# h-bridge2-smd-001.net
KiCad netlist of a schematic drawn in EAGLE
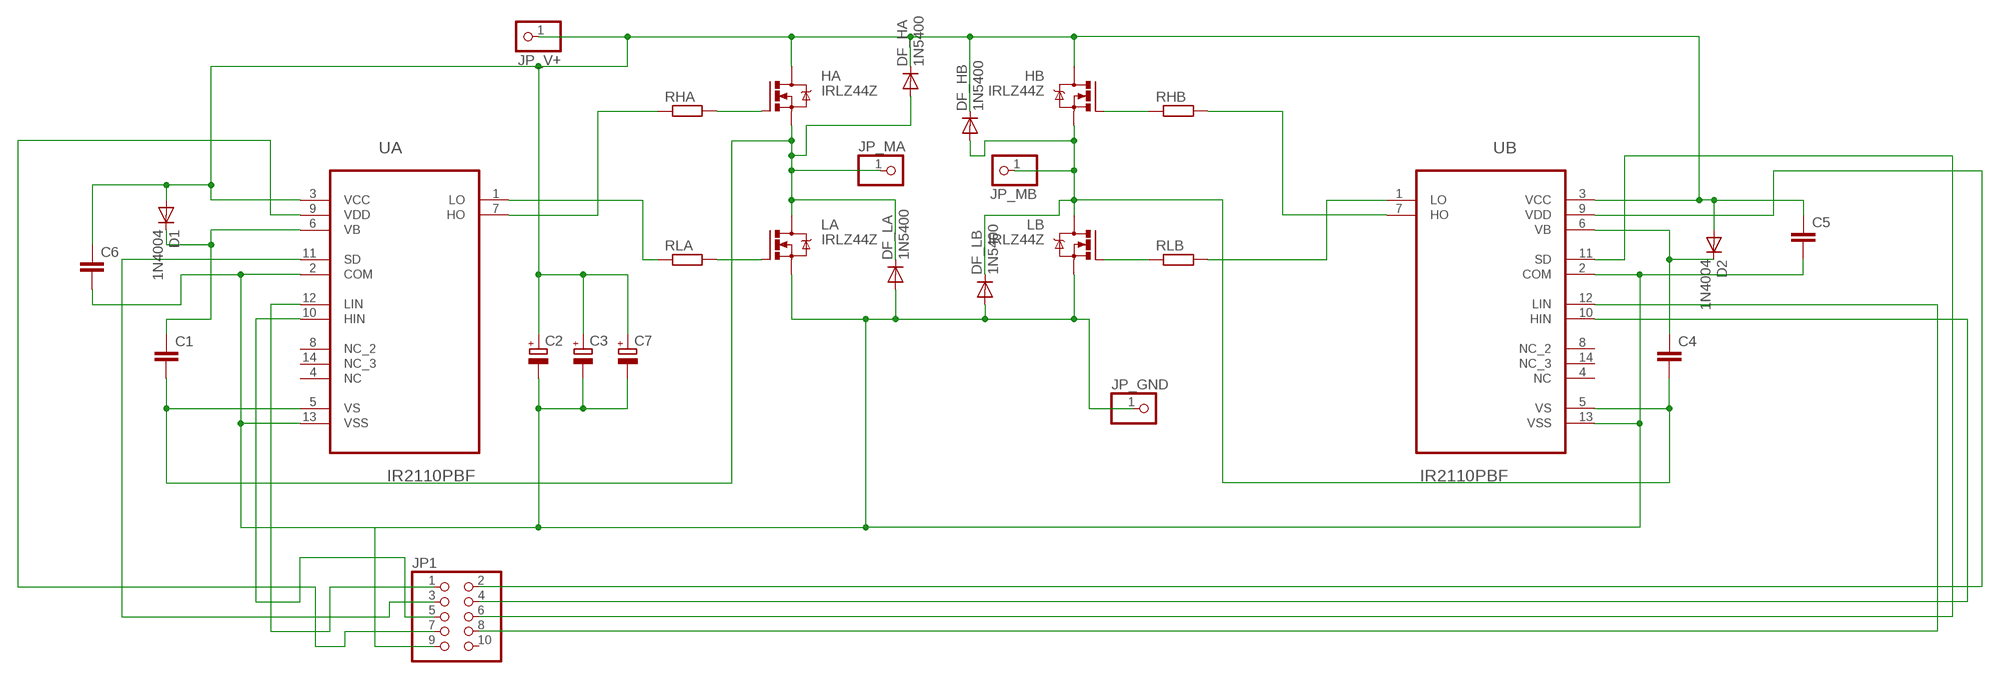
[diagram p0: schematic, sheet 1]

(export (version "E")
  (design (tool "Eeschema 10.0.6"))
  (components
    (comp (ref "C1")
      (value "C-EU025-025X050")
      (footprint "eagle-import:C025-025X050")
      (libsource (lib "eagle-import") (part "C-EU025-025X050"))
    )
    (comp (ref "C2")
      (value "CPOL-EUE5-13")
      (footprint "eagle-import:E5-13")
      (libsource (lib "eagle-import") (part "CPOL-EUE5-13"))
    )
    (comp (ref "C3")
      (value "CPOL-EUE5-13")
      (footprint "eagle-import:E5-13")
      (libsource (lib "eagle-import") (part "CPOL-EUE5-13"))
    )
    (comp (ref "C4")
      (value "C-EU025-025X050")
      (footprint "eagle-import:C025-025X050")
      (libsource (lib "eagle-import") (part "C-EU025-025X050"))
    )
    (comp (ref "C5")
      (value "C-EU025-025X050")
      (footprint "eagle-import:C025-025X050")
      (libsource (lib "eagle-import") (part "C-EU025-025X050"))
    )
    (comp (ref "C6")
      (value "C-EU025-025X050")
      (footprint "eagle-import:C025-025X050")
      (libsource (lib "eagle-import") (part "C-EU025-025X050"))
    )
    (comp (ref "C7")
      (value "CPOL-EUE5-13")
      (footprint "eagle-import:E5-13")
      (libsource (lib "eagle-import") (part "CPOL-EUE5-13"))
    )
    (comp (ref "D1")
      (value "1N4004")
      (footprint "eagle-import:DO41-10")
      (libsource (lib "eagle-import") (part "1N4004"))
    )
    (comp (ref "D2")
      (value "1N4004")
      (footprint "eagle-import:DO41-10")
      (libsource (lib "eagle-import") (part "1N4004"))
    )
    (comp (ref "DF_HA")
      (value "1N5400")
      (footprint "eagle-import:DO201-15")
      (libsource (lib "eagle-import") (part "1N5400"))
    )
    (comp (ref "DF_HB")
      (value "1N5400")
      (footprint "eagle-import:DO201-15")
      (libsource (lib "eagle-import") (part "1N5400"))
    )
    (comp (ref "DF_LA")
      (value "1N5400")
      (footprint "eagle-import:DO201-15")
      (libsource (lib "eagle-import") (part "1N5400"))
    )
    (comp (ref "DF_LB")
      (value "1N5400")
      (footprint "eagle-import:DO201-15")
      (libsource (lib "eagle-import") (part "1N5400"))
    )
    (comp (ref "HA")
      (value "IRLZ44Z")
      (footprint "eagle-import:TO220BH")
      (libsource (lib "eagle-import") (part "IRLZ44Z"))
    )
    (comp (ref "HB")
      (value "IRLZ44Z")
      (footprint "eagle-import:TO220BH")
      (libsource (lib "eagle-import") (part "IRLZ44Z"))
    )
    (comp (ref "JP1")
      (value "PINHD-2X5")
      (footprint "eagle-import:2X05")
      (libsource (lib "eagle-import") (part "PINHD-2X5"))
    )
    (comp (ref "JP_GND")
      (value "PINHD-1X1")
      (footprint "eagle-import:1X01")
      (libsource (lib "eagle-import") (part "PINHD-1X1"))
    )
    (comp (ref "JP_MA")
      (value "PINHD-1X1")
      (footprint "eagle-import:1X01")
      (libsource (lib "eagle-import") (part "PINHD-1X1"))
    )
    (comp (ref "JP_MB")
      (value "PINHD-1X1")
      (footprint "eagle-import:1X01")
      (libsource (lib "eagle-import") (part "PINHD-1X1"))
    )
    (comp (ref "JP_V+")
      (value "PINHD-1X1")
      (footprint "eagle-import:1X01")
      (libsource (lib "eagle-import") (part "PINHD-1X1"))
    )
    (comp (ref "LA")
      (value "IRLZ44Z")
      (footprint "eagle-import:TO220BH")
      (libsource (lib "eagle-import") (part "IRLZ44Z"))
    )
    (comp (ref "LB")
      (value "IRLZ44Z")
      (footprint "eagle-import:TO220BH")
      (libsource (lib "eagle-import") (part "IRLZ44Z"))
    )
    (comp (ref "RHA")
      (value "R-EU_0411/15")
      (footprint "eagle-import:0411_15")
      (libsource (lib "eagle-import") (part "R-EU_0411/15"))
    )
    (comp (ref "RHB")
      (value "R-EU_0411/15")
      (footprint "eagle-import:0411_15")
      (libsource (lib "eagle-import") (part "R-EU_0411/15"))
    )
    (comp (ref "RLA")
      (value "R-EU_0411/15")
      (footprint "eagle-import:0411_15")
      (libsource (lib "eagle-import") (part "R-EU_0411/15"))
    )
    (comp (ref "RLB")
      (value "R-EU_0411/15")
      (footprint "eagle-import:0411_15")
      (libsource (lib "eagle-import") (part "R-EU_0411/15"))
    )
    (comp (ref "UA")
      (value "IR2110PBF")
      (footprint "eagle-import:DIP254P762X533-14")
      (libsource (lib "eagle-import") (part "IR2110PBF"))
    )
    (comp (ref "UB")
      (value "IR2110PBF")
      (footprint "eagle-import:DIP254P762X533-14")
      (libsource (lib "eagle-import") (part "IR2110PBF"))
    )
  )
  (nets
    (net (code "1") (name "Net-(HA-PadG)") (class "Default")
      (node (ref "HA") (pin "G") (pinfunction "G_G") (pintype "passive"))
      (node (ref "RHA") (pin "2") (pinfunction "2_2") (pintype "passive"))
    )
    (net (code "2") (name "Net-(HB-PadG)") (class "Default")
      (node (ref "HB") (pin "G") (pinfunction "G_G") (pintype "passive"))
      (node (ref "RHB") (pin "1") (pinfunction "1_1") (pintype "passive"))
    )
    (net (code "3") (name "Net-(LA-PadG)") (class "Default")
      (node (ref "LA") (pin "G") (pinfunction "G_G") (pintype "passive"))
      (node (ref "RLA") (pin "2") (pinfunction "2_2") (pintype "passive"))
    )
    (net (code "4") (name "Net-(LB-PadG)") (class "Default")
      (node (ref "LB") (pin "G") (pinfunction "G_G") (pintype "passive"))
      (node (ref "RLB") (pin "1") (pinfunction "1_1") (pintype "passive"))
    )
    (net (code "5") (name "Net-(UA-COM)") (class "Default")
      (node (ref "C2") (pin "-") (pinfunction "-_-") (pintype "passive"))
      (node (ref "C3") (pin "-") (pinfunction "-_-") (pintype "passive"))
      (node (ref "C5") (pin "2") (pinfunction "2_2") (pintype "passive"))
      (node (ref "C6") (pin "2") (pinfunction "2_2") (pintype "passive"))
      (node (ref "C7") (pin "-") (pinfunction "-_-") (pintype "passive"))
      (node (ref "DF_LA") (pin "A") (pinfunction "A_A") (pintype "passive"))
      (node (ref "DF_LB") (pin "A") (pinfunction "A_A") (pintype "passive"))
      (node (ref "JP1") (pin "9") (pinfunction "9_9") (pintype "passive"))
      (node (ref "JP_GND") (pin "1") (pinfunction "1_1") (pintype "passive"))
      (node (ref "LA") (pin "S") (pinfunction "S_S") (pintype "passive"))
      (node (ref "LB") (pin "S") (pinfunction "S_S") (pintype "passive"))
      (node (ref "UA") (pin "13") (pinfunction "VSS_13") (pintype "power_in"))
      (node (ref "UA") (pin "2") (pinfunction "COM_2") (pintype "passive"))
      (node (ref "UB") (pin "13") (pinfunction "VSS_13") (pintype "power_in"))
      (node (ref "UB") (pin "2") (pinfunction "COM_2") (pintype "passive"))
    )
    (net (code "6") (name "Net-(UA-HIN)") (class "Default")
      (node (ref "JP1") (pin "5") (pinfunction "5_5") (pintype "passive"))
      (node (ref "UA") (pin "10") (pinfunction "HIN_10") (pintype "input"))
    )
    (net (code "7") (name "Net-(UA-HO)") (class "Default")
      (node (ref "RHA") (pin "1") (pinfunction "1_1") (pintype "passive"))
      (node (ref "UA") (pin "7") (pinfunction "HO_7") (pintype "output"))
    )
    (net (code "8") (name "Net-(UA-LIN)") (class "Default")
      (node (ref "JP1") (pin "1") (pinfunction "1_1") (pintype "passive"))
      (node (ref "UA") (pin "12") (pinfunction "LIN_12") (pintype "input"))
    )
    (net (code "9") (name "Net-(UA-LO)") (class "Default")
      (node (ref "RLA") (pin "1") (pinfunction "1_1") (pintype "passive"))
      (node (ref "UA") (pin "1") (pinfunction "LO_1") (pintype "output"))
    )
    (net (code "10") (name "Net-(UA-SD)") (class "Default")
      (node (ref "JP1") (pin "3") (pinfunction "3_3") (pintype "passive"))
      (node (ref "UA") (pin "11") (pinfunction "SD_11") (pintype "input"))
    )
    (net (code "11") (name "Net-(UA-VB)") (class "Default")
      (node (ref "C1") (pin "1") (pinfunction "1_1") (pintype "passive"))
      (node (ref "D1") (pin "C") (pinfunction "C_C") (pintype "passive"))
      (node (ref "UA") (pin "6") (pinfunction "VB_6") (pintype "power_in"))
    )
    (net (code "12") (name "Net-(UA-VCC)") (class "Default")
      (node (ref "C2") (pin "+") (pinfunction "+_+") (pintype "passive"))
      (node (ref "C3") (pin "+") (pinfunction "+_+") (pintype "passive"))
      (node (ref "C5") (pin "1") (pinfunction "1_1") (pintype "passive"))
      (node (ref "C6") (pin "1") (pinfunction "1_1") (pintype "passive"))
      (node (ref "C7") (pin "+") (pinfunction "+_+") (pintype "passive"))
      (node (ref "D1") (pin "A") (pinfunction "A_A") (pintype "passive"))
      (node (ref "D2") (pin "A") (pinfunction "A_A") (pintype "passive"))
      (node (ref "DF_HA") (pin "C") (pinfunction "C_C") (pintype "passive"))
      (node (ref "DF_HB") (pin "C") (pinfunction "C_C") (pintype "passive"))
      (node (ref "HA") (pin "D") (pinfunction "D_D") (pintype "passive"))
      (node (ref "HB") (pin "D") (pinfunction "D_D") (pintype "passive"))
      (node (ref "JP_V+") (pin "1") (pinfunction "1_1") (pintype "passive"))
      (node (ref "UA") (pin "3") (pinfunction "VCC_3") (pintype "power_in"))
      (node (ref "UB") (pin "3") (pinfunction "VCC_3") (pintype "power_in"))
    )
    (net (code "13") (name "Net-(UA-VDD)") (class "Default")
      (node (ref "JP1") (pin "7") (pinfunction "7_7") (pintype "passive"))
      (node (ref "UA") (pin "9") (pinfunction "VDD_9") (pintype "power_in"))
    )
    (net (code "14") (name "Net-(UA-VS)") (class "Default")
      (node (ref "C1") (pin "2") (pinfunction "2_2") (pintype "passive"))
      (node (ref "DF_HA") (pin "A") (pinfunction "A_A") (pintype "passive"))
      (node (ref "DF_LA") (pin "C") (pinfunction "C_C") (pintype "passive"))
      (node (ref "HA") (pin "S") (pinfunction "S_S") (pintype "passive"))
      (node (ref "JP_MA") (pin "1") (pinfunction "1_1") (pintype "passive"))
      (node (ref "LA") (pin "D") (pinfunction "D_D") (pintype "passive"))
      (node (ref "UA") (pin "5") (pinfunction "VS_5") (pintype "power_in"))
    )
    (net (code "15") (name "Net-(UB-HIN)") (class "Default")
      (node (ref "JP1") (pin "4") (pinfunction "4_4") (pintype "passive"))
      (node (ref "UB") (pin "10") (pinfunction "HIN_10") (pintype "input"))
    )
    (net (code "16") (name "Net-(UB-HO)") (class "Default")
      (node (ref "RHB") (pin "2") (pinfunction "2_2") (pintype "passive"))
      (node (ref "UB") (pin "7") (pinfunction "HO_7") (pintype "output"))
    )
    (net (code "17") (name "Net-(UB-LIN)") (class "Default")
      (node (ref "JP1") (pin "8") (pinfunction "8_8") (pintype "passive"))
      (node (ref "UB") (pin "12") (pinfunction "LIN_12") (pintype "input"))
    )
    (net (code "18") (name "Net-(UB-LO)") (class "Default")
      (node (ref "RLB") (pin "2") (pinfunction "2_2") (pintype "passive"))
      (node (ref "UB") (pin "1") (pinfunction "LO_1") (pintype "output"))
    )
    (net (code "19") (name "Net-(UB-SD)") (class "Default")
      (node (ref "JP1") (pin "6") (pinfunction "6_6") (pintype "passive"))
      (node (ref "UB") (pin "11") (pinfunction "SD_11") (pintype "input"))
    )
    (net (code "20") (name "Net-(UB-VB)") (class "Default")
      (node (ref "C4") (pin "1") (pinfunction "1_1") (pintype "passive"))
      (node (ref "D2") (pin "C") (pinfunction "C_C") (pintype "passive"))
      (node (ref "UB") (pin "6") (pinfunction "VB_6") (pintype "power_in"))
    )
    (net (code "21") (name "Net-(UB-VDD)") (class "Default")
      (node (ref "JP1") (pin "2") (pinfunction "2_2") (pintype "passive"))
      (node (ref "UB") (pin "9") (pinfunction "VDD_9") (pintype "power_in"))
    )
    (net (code "22") (name "Net-(UB-VS)") (class "Default")
      (node (ref "C4") (pin "2") (pinfunction "2_2") (pintype "passive"))
      (node (ref "DF_HB") (pin "A") (pinfunction "A_A") (pintype "passive"))
      (node (ref "DF_LB") (pin "C") (pinfunction "C_C") (pintype "passive"))
      (node (ref "HB") (pin "S") (pinfunction "S_S") (pintype "passive"))
      (node (ref "JP_MB") (pin "1") (pinfunction "1_1") (pintype "passive"))
      (node (ref "LB") (pin "D") (pinfunction "D_D") (pintype "passive"))
      (node (ref "UB") (pin "5") (pinfunction "VS_5") (pintype "power_in"))
    )
    (net (code "23") (name "unconnected-(JP1-Pad10)") (class "Default")
      (node (ref "JP1") (pin "10") (pinfunction "10_10") (pintype "passive"))
    )
    (net (code "24") (name "unconnected-(UA-NC-Pad4)") (class "Default")
      (node (ref "UA") (pin "4") (pinfunction "NC_4") (pintype "no_connect"))
    )
    (net (code "25") (name "unconnected-(UA-NC_2-Pad8)") (class "Default")
      (node (ref "UA") (pin "8") (pinfunction "NC_2_8") (pintype "no_connect"))
    )
    (net (code "26") (name "unconnected-(UA-NC_3-Pad14)") (class "Default")
      (node (ref "UA") (pin "14") (pinfunction "NC_3_14") (pintype "no_connect"))
    )
    (net (code "27") (name "unconnected-(UB-NC-Pad4)") (class "Default")
      (node (ref "UB") (pin "4") (pinfunction "NC_4") (pintype "no_connect"))
    )
    (net (code "28") (name "unconnected-(UB-NC_2-Pad8)") (class "Default")
      (node (ref "UB") (pin "8") (pinfunction "NC_2_8") (pintype "no_connect"))
    )
    (net (code "29") (name "unconnected-(UB-NC_3-Pad14)") (class "Default")
      (node (ref "UB") (pin "14") (pinfunction "NC_3_14") (pintype "no_connect"))
    )
  )
)
